# PCB_Schematic.net
KiCad netlist of a schematic drawn in Altium Designer
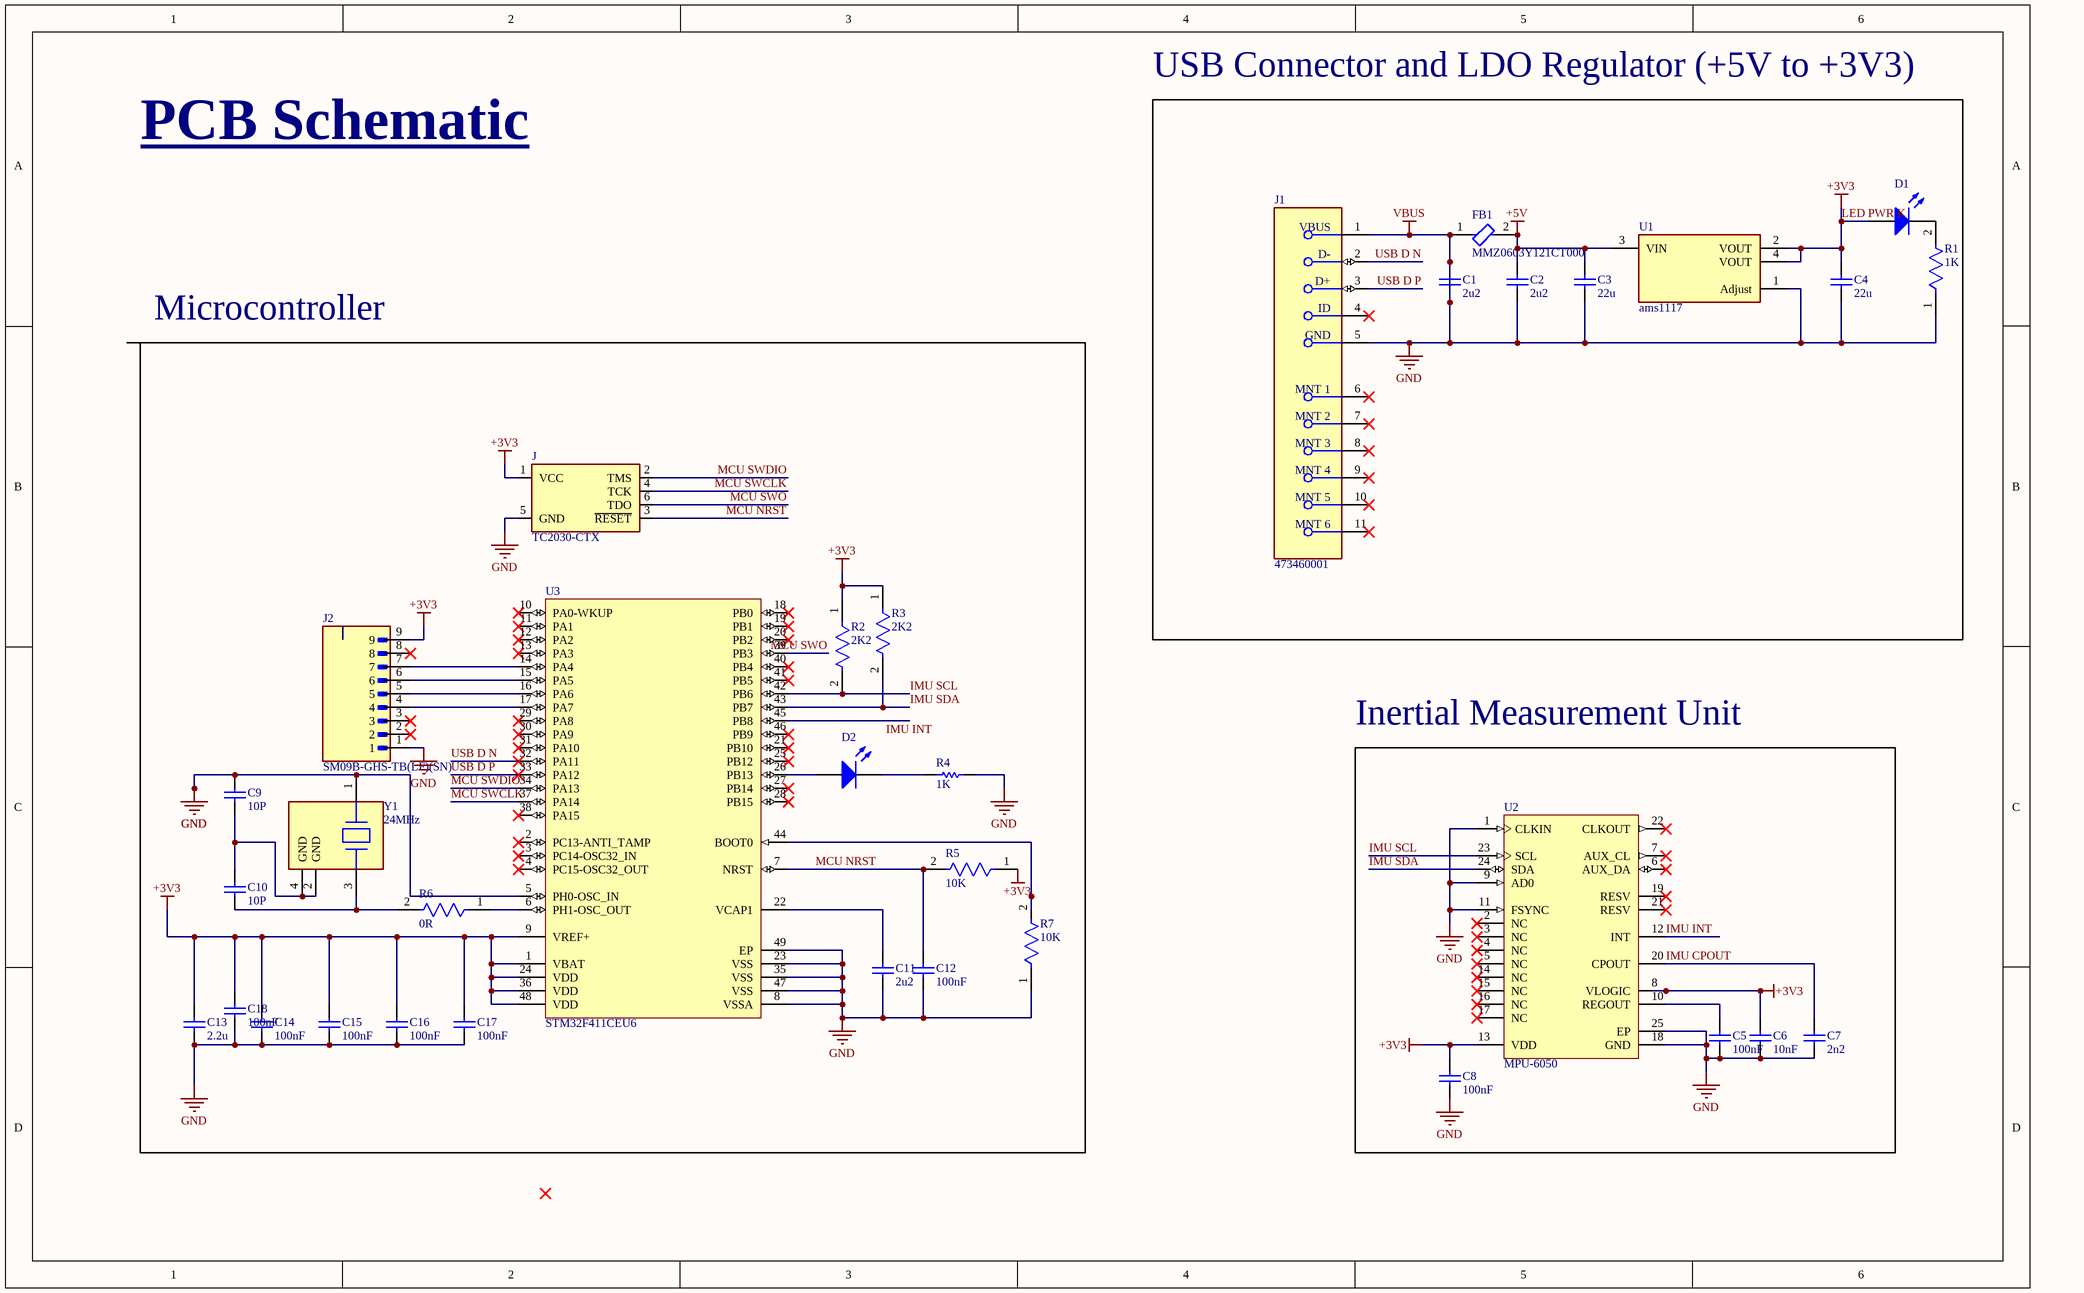
[diagram p0: PCB Schematic.SchDoc]

(export (version "E")
  (design (tool "Eeschema 10.0.6"))
  (components
    (comp (ref "C1")
      (value "2u2")
      (footprint "CAPC1210(3225)100_L")
      (description "CAP 100nF 16V ±5% 1210 (3225 Metric) Thickness 1mm SMD")
      (fields (field (name "TOLERANCE") "Â±5%"))
      (libsource (lib "Altium Content Vault") (part "CAP"))
    )
    (comp (ref "C2")
      (value "2u2")
      (footprint "CAPC1210(3225)100_L")
      (description "CAP 100nF 16V ±5% 1210 (3225 Metric) Thickness 1mm SMD")
      (fields (field (name "TOLERANCE") "Â±5%"))
      (libsource (lib "Altium Content Vault") (part "CAP"))
    )
    (comp (ref "C3")
      (value "22u")
      (footprint "CAPC1210(3225)100_L")
      (description "CAP 100nF 16V ±5% 1210 (3225 Metric) Thickness 1mm SMD")
      (fields (field (name "TOLERANCE") "Â±5%"))
      (libsource (lib "Altium Content Vault") (part "CAP"))
    )
    (comp (ref "C4")
      (value "22u")
      (footprint "CAPC1210(3225)100_L")
      (description "CAP 100nF 16V ±5% 1210 (3225 Metric) Thickness 1mm SMD")
      (fields (field (name "TOLERANCE") "Â±5%"))
      (libsource (lib "Altium Content Vault") (part "CAP"))
    )
    (comp (ref "C5")
      (value "100nF")
      (footprint "CAPC1210(3225)100_L")
      (description "CAP 100nF 16V ±5% 1210 (3225 Metric) Thickness 1mm SMD")
      (fields (field (name "TOLERANCE") "Â±5%"))
      (libsource (lib "Altium Content Vault") (part "CAP"))
    )
    (comp (ref "C6")
      (value "10nF")
      (footprint "CAPC1210(3225)100_L")
      (description "CAP 100nF 16V ±5% 1210 (3225 Metric) Thickness 1mm SMD")
      (fields (field (name "TOLERANCE") "Â±5%"))
      (libsource (lib "Altium Content Vault") (part "CAP"))
    )
    (comp (ref "C7")
      (value "2n2")
      (footprint "CAPC1210(3225)100_L")
      (description "CAP 100nF 16V ±5% 1210 (3225 Metric) Thickness 1mm SMD")
      (fields (field (name "TOLERANCE") "Â±5%"))
      (libsource (lib "Altium Content Vault") (part "CAP"))
    )
    (comp (ref "C8")
      (value "100nF")
      (footprint "CAPC1210(3225)100_L")
      (description "CAP 100nF 16V ±5% 1210 (3225 Metric) Thickness 1mm SMD")
      (fields (field (name "TOLERANCE") "Â±5%"))
      (libsource (lib "Altium Content Vault") (part "CAP"))
    )
    (comp (ref "C9")
      (value "10P")
      (footprint "CAPC1210(3225)100_L")
      (description "2.2u")
      (fields (field (name "TOLERANCE") "Â±5%"))
      (libsource (lib "Altium Content Vault") (part "CAP"))
    )
    (comp (ref "C10")
      (value "10P")
      (footprint "CAPC1210(3225)100_L")
      (description "2.2u")
      (fields (field (name "TOLERANCE") "Â±5%"))
      (libsource (lib "Altium Content Vault") (part "CAP"))
    )
    (comp (ref "C11")
      (value "2u2")
      (footprint "CAPC1210(3225)100_L")
      (description "CAP 100nF 16V ±5% 1210 (3225 Metric) Thickness 1mm SMD")
      (fields (field (name "TOLERANCE") "Â±5%"))
      (libsource (lib "Altium Content Vault") (part "CAP"))
    )
    (comp (ref "C12")
      (value "100nF")
      (footprint "CAPC1210(3225)100_L")
      (description "CAP 100nF 16V ±5% 1210 (3225 Metric) Thickness 1mm SMD")
      (fields (field (name "TOLERANCE") "Â±5%"))
      (libsource (lib "Altium Content Vault") (part "CAP"))
    )
    (comp (ref "C13")
      (value "2.2u")
      (footprint "CAPC1210(3225)100_L")
      (fields (field (name "TOLERANCE") "Â±5%"))
      (libsource (lib "Altium Content Vault") (part "CAP"))
    )
    (comp (ref "C14")
      (value "100nF")
      (footprint "CAPC1210(3225)100_L")
      (fields (field (name "TOLERANCE") "Â±5%"))
      (libsource (lib "Altium Content Vault") (part "CAP"))
    )
    (comp (ref "C15")
      (value "100nF")
      (footprint "CAPC1210(3225)100_L")
      (fields (field (name "TOLERANCE") "Â±5%"))
      (libsource (lib "Altium Content Vault") (part "CAP"))
    )
    (comp (ref "C16")
      (value "100nF")
      (footprint "CAPC1210(3225)100_L")
      (fields (field (name "TOLERANCE") "Â±5%"))
      (libsource (lib "Altium Content Vault") (part "CAP"))
    )
    (comp (ref "C17")
      (value "100nF")
      (footprint "CAPC1210(3225)100_L")
      (description "CAP 100nF 16V ±5% 1210 (3225 Metric) Thickness 1mm SMD")
      (fields (field (name "TOLERANCE") "Â±5%"))
      (libsource (lib "Altium Content Vault") (part "CAP"))
    )
    (comp (ref "C18")
      (value "100nF")
      (footprint "CAPC1210(3225)100_L")
      (fields (field (name "TOLERANCE") "Â±5%"))
      (libsource (lib "Altium Content Vault") (part "CAP"))
    )
    (comp (ref "D1")
      (value "Light-Emitting Diode")
      (libsource (lib "Simulation Generic Components") (part "LED"))
    )
    (comp (ref "D2")
      (value "Light-Emitting Diode")
      (libsource (lib "Simulation Generic Components") (part "LED"))
    )
    (comp (ref "FB1")
      (value "MMZ0603Y121CT000")
      (footprint "FP-MMZ0603-IPC_C")
      (description "Signal Line Ferrite Bead 120Ω @ 100MHz 200mA DCR 390mΩ SMD 0201")
      (fields (field (name "TOLERANCE") "25%"))
      (libsource (lib "Altium Content Vault") (part "5f30dd21d616792df468990f7003faa"))
    )
    (comp (ref "J")
      (value "TC2030-CTX")
      (footprint "TC2030-IDC-NL")
      (description "CortexÂ® Plug-Of-Nailsâ„¢ Adapter Cable")
      (fields (field (name "MF") "Tag-Connect LLC"))
      (libsource (lib "TC2030-CTX") (part "TC2030-CTX"))
    )
    (comp (ref "J1")
      (value "473460001")
      (footprint "FP-473460001-MFG")
      (description "USB - micro B USB 2.0 Receptacle Connector 5 Position Surface Mount, Right Angle")
      (fields (field (name "OCTOPART") "https://octopart.com/47346-0001-molex-7164928"))
      (libsource (lib "Altium Content Vault") (part "53ae1f1d9b557310b43ca686e5bb76a"))
    )
    (comp (ref "J2")
      (value "SM09B-GHS-TB(LF)(SN)")
      (footprint "JST_SM09B-GHS-TB(LF)(SN)")
      (fields (field (name "MF") "JST") (field (name "MP") "SM09B-GHS-TB (LF)(SN)"))
      (libsource (lib "SM09B-GHS-TB_LF__SN_") (part "SM09B-GHS-TB(LF)(SN)"))
    )
    (comp (ref "R1")
      (value "1K")
      (footprint "FP-AC0603-IPC_A")
      (description "RES 10kΩ 5.00% 0.2W 0603")
      (libsource (lib "Altium Content Vault") (part "1029c3af85768c4190bb7ad29bc67b5"))
    )
    (comp (ref "R2")
      (value "2K2")
      (footprint "FP-AC0603-IPC_A")
      (description "RES 10kΩ 5.00% 0.2W 0603")
      (libsource (lib "Altium Content Vault") (part "1029c3af85768c4190bb7ad29bc67b5"))
    )
    (comp (ref "R3")
      (value "2K2")
      (footprint "FP-AC0603-IPC_A")
      (description "RES 10kΩ 5.00% 0.2W 0603")
      (libsource (lib "Altium Content Vault") (part "1029c3af85768c4190bb7ad29bc67b5"))
    )
    (comp (ref "R4")
      (value "1K")
      (description "Resistor")
      (libsource (lib "Simulation Generic Components") (part "Resistor"))
    )
    (comp (ref "R5")
      (value "10K")
      (footprint "FP-AC0603-IPC_A")
      (description "RES 10kΩ 5.00% 0.2W 0603")
      (libsource (lib "Altium Content Vault") (part "1029c3af85768c4190bb7ad29bc67b5"))
    )
    (comp (ref "R6")
      (value "0R")
      (footprint "FP-AC0603-IPC_A")
      (description "RES 10kΩ 5.00% 0.2W 0603")
      (libsource (lib "Altium Content Vault") (part "1029c3af85768c4190bb7ad29bc67b5"))
    )
    (comp (ref "R7")
      (value "10K")
      (footprint "FP-AC0603-IPC_A")
      (description "RES 10kΩ 5.00% 0.2W 0603")
      (libsource (lib "Altium Content Vault") (part "1029c3af85768c4190bb7ad29bc67b5"))
    )
    (comp (ref "U1")
      (value "ams1117")
      (footprint "FP-ams1117-IPC_C")
      (description "1A LOW DROPOUT VOLTAGE REGULATOR")
      (libsource (lib "Altium Content Vault") (part "59ad430b93a2c51b3e6ee7c3b069677"))
    )
    (comp (ref "U2")
      (value "MPU-6050")
      (footprint "IS-QFN-24_V")
      (fields (field (name "MANUFACTURER") "InvenSense"))
      (libsource (lib "Altium Content Vault") (part "IS-MPU-6050-QFN-24"))
    )
    (comp (ref "U3")
      (value "STM32F411CEU6")
      (footprint "STM-UFQFPN48_L")
      (libsource (lib "Altium Content Vault") (part "MC-ARM-STM32F411-UFQFPN48"))
    )
    (comp (ref "Y1")
      (value "24MHz")
      (footprint "FP-ABM10AIG-MFG")
      (description "Crystal 24MHz ±30ppm 10pF SMD-4 2.5mm x 2mm Automotive")
      (libsource (lib "Altium Content Vault") (part "40c3c19da1ce8e2d75e34138d1085e7"))
    )
  )
  (nets
    (net (code "1") (name "+3V3") (class "Default")
      (node (ref "C13") (pin "2") (pinfunction "2_2") (pintype "passive"))
      (node (ref "C14") (pin "2") (pinfunction "2_2") (pintype "passive"))
      (node (ref "C15") (pin "2") (pinfunction "2_2") (pintype "passive"))
      (node (ref "C16") (pin "2") (pinfunction "2_2") (pintype "passive"))
      (node (ref "C17") (pin "2") (pinfunction "2_2") (pintype "passive"))
      (node (ref "C18") (pin "2") (pinfunction "2_2") (pintype "passive"))
      (node (ref "C4") (pin "2") (pinfunction "2_2") (pintype "passive"))
      (node (ref "C6") (pin "2") (pinfunction "2_2") (pintype "passive"))
      (node (ref "C8") (pin "2") (pinfunction "2_2") (pintype "passive"))
      (node (ref "D1") (pin "1") (pinfunction "A_1") (pintype "passive"))
      (node (ref "J") (pin "1") (pinfunction "VCC_1") (pintype "bidirectional"))
      (node (ref "J2") (pin "9") (pinfunction "9_9") (pintype "passive"))
      (node (ref "R2") (pin "1") (pinfunction "1_1") (pintype "passive"))
      (node (ref "R3") (pin "1") (pinfunction "1_1") (pintype "passive"))
      (node (ref "R5") (pin "1") (pinfunction "1_1") (pintype "passive"))
      (node (ref "U1") (pin "2") (pinfunction "VOUT_2") (pintype "passive"))
      (node (ref "U1") (pin "4") (pinfunction "VOUT_4") (pintype "passive"))
      (node (ref "U2") (pin "13") (pinfunction "VDD_13") (pintype "power_in"))
      (node (ref "U2") (pin "8") (pinfunction "VLOGIC_8") (pintype "power_in"))
      (node (ref "U3") (pin "1") (pinfunction "VBAT_1") (pintype "power_in"))
      (node (ref "U3") (pin "24") (pinfunction "VDD_24") (pintype "power_in"))
      (node (ref "U3") (pin "36") (pinfunction "VDD_36") (pintype "power_in"))
      (node (ref "U3") (pin "48") (pinfunction "VDD_48") (pintype "power_in"))
      (node (ref "U3") (pin "9") (pinfunction "VREF+_9") (pintype "power_in"))
    )
    (net (code "2") (name "+5V") (class "Default")
      (node (ref "C2") (pin "2") (pinfunction "2_2") (pintype "passive"))
      (node (ref "C3") (pin "2") (pinfunction "2_2") (pintype "passive"))
      (node (ref "FB1") (pin "2") (pinfunction "2_2") (pintype "passive"))
      (node (ref "U1") (pin "3") (pinfunction "VIN_3") (pintype "power_in"))
    )
    (net (code "3") (name "/IMU CPOUT") (class "Default")
      (node (ref "C7") (pin "2") (pinfunction "2_2") (pintype "passive"))
      (node (ref "U2") (pin "20") (pinfunction "CPOUT_20") (pintype "passive"))
    )
    (net (code "4") (name "/IMU INT") (class "Default")
      (node (ref "U2") (pin "12") (pinfunction "INT_12") (pintype "open_collector"))
      (node (ref "U3") (pin "45") (pinfunction "PB8_45") (pintype "bidirectional"))
    )
    (net (code "5") (name "/IMU SCL") (class "Default")
      (node (ref "R2") (pin "2") (pinfunction "2_2") (pintype "passive"))
      (node (ref "U2") (pin "23") (pinfunction "SCL_23") (pintype "input"))
      (node (ref "U3") (pin "42") (pinfunction "PB6_42") (pintype "bidirectional"))
    )
    (net (code "6") (name "/IMU SDA") (class "Default")
      (node (ref "R3") (pin "2") (pinfunction "2_2") (pintype "passive"))
      (node (ref "U2") (pin "24") (pinfunction "SDA_24") (pintype "bidirectional"))
      (node (ref "U3") (pin "43") (pinfunction "PB7_43") (pintype "bidirectional"))
    )
    (net (code "7") (name "/MCU NRST") (class "Default")
      (node (ref "C12") (pin "2") (pinfunction "2_2") (pintype "passive"))
      (node (ref "J") (pin "3") (pinfunction "~{RESET}_3") (pintype "bidirectional"))
      (node (ref "R5") (pin "2") (pinfunction "2_2") (pintype "passive"))
      (node (ref "U3") (pin "7") (pinfunction "NRST_7") (pintype "bidirectional"))
    )
    (net (code "8") (name "/MCU SWCLK") (class "Default")
      (node (ref "J") (pin "4") (pinfunction "TCK_4") (pintype "bidirectional"))
      (node (ref "U3") (pin "37") (pinfunction "PA14_37") (pintype "bidirectional"))
    )
    (net (code "9") (name "/MCU SWDIO") (class "Default")
      (node (ref "J") (pin "2") (pinfunction "TMS_2") (pintype "bidirectional"))
      (node (ref "U3") (pin "34") (pinfunction "PA13_34") (pintype "bidirectional"))
    )
    (net (code "10") (name "/MCU SWO") (class "Default")
      (node (ref "J") (pin "6") (pinfunction "TDO_6") (pintype "bidirectional"))
      (node (ref "U3") (pin "39") (pinfunction "PB3_39") (pintype "bidirectional"))
    )
    (net (code "11") (name "/USB D N") (class "Default")
      (node (ref "J1") (pin "2") (pinfunction "D-_2") (pintype "bidirectional"))
      (node (ref "U3") (pin "32") (pinfunction "PA11_32") (pintype "bidirectional"))
    )
    (net (code "12") (name "/USB D P") (class "Default")
      (node (ref "J1") (pin "3") (pinfunction "D+_3") (pintype "bidirectional"))
      (node (ref "U3") (pin "33") (pinfunction "PA12_33") (pintype "bidirectional"))
    )
    (net (code "13") (name "GND") (class "Default")
      (node (ref "C1") (pin "1") (pinfunction "1_1") (pintype "passive"))
      (node (ref "C1") (pin "2") (pinfunction "2_2") (pintype "passive"))
      (node (ref "C11") (pin "1") (pinfunction "1_1") (pintype "passive"))
      (node (ref "C12") (pin "1") (pinfunction "1_1") (pintype "passive"))
      (node (ref "C13") (pin "1") (pinfunction "1_1") (pintype "passive"))
      (node (ref "C14") (pin "1") (pinfunction "1_1") (pintype "passive"))
      (node (ref "C15") (pin "1") (pinfunction "1_1") (pintype "passive"))
      (node (ref "C16") (pin "1") (pinfunction "1_1") (pintype "passive"))
      (node (ref "C17") (pin "1") (pinfunction "1_1") (pintype "passive"))
      (node (ref "C18") (pin "1") (pinfunction "1_1") (pintype "passive"))
      (node (ref "C2") (pin "1") (pinfunction "1_1") (pintype "passive"))
      (node (ref "C3") (pin "1") (pinfunction "1_1") (pintype "passive"))
      (node (ref "C4") (pin "1") (pinfunction "1_1") (pintype "passive"))
      (node (ref "C5") (pin "1") (pinfunction "1_1") (pintype "passive"))
      (node (ref "C6") (pin "1") (pinfunction "1_1") (pintype "passive"))
      (node (ref "C7") (pin "1") (pinfunction "1_1") (pintype "passive"))
      (node (ref "C8") (pin "1") (pinfunction "1_1") (pintype "passive"))
      (node (ref "C9") (pin "1") (pinfunction "1_1") (pintype "passive"))
      (node (ref "FB1") (pin "1") (pinfunction "1_1") (pintype "passive"))
      (node (ref "J") (pin "5") (pinfunction "GND_5") (pintype "bidirectional"))
      (node (ref "J1") (pin "1") (pinfunction "VBUS_1") (pintype "power_in"))
      (node (ref "J1") (pin "5") (pinfunction "GND_5") (pintype "power_in"))
      (node (ref "J2") (pin "1") (pinfunction "1_1") (pintype "passive"))
      (node (ref "R1") (pin "1") (pinfunction "1_1") (pintype "passive"))
      (node (ref "R4") (pin "1") (pinfunction "1_1") (pintype "passive"))
      (node (ref "R7") (pin "1") (pinfunction "1_1") (pintype "passive"))
      (node (ref "U1") (pin "1") (pinfunction "Adjust_1") (pintype "passive"))
      (node (ref "U2") (pin "1") (pinfunction "CLKIN_1") (pintype "input"))
      (node (ref "U2") (pin "11") (pinfunction "FSYNC_11") (pintype "input"))
      (node (ref "U2") (pin "18") (pinfunction "GND_18") (pintype "power_in"))
      (node (ref "U2") (pin "25") (pinfunction "EP_25") (pintype "power_in"))
      (node (ref "U2") (pin "9") (pinfunction "AD0_9") (pintype "input"))
      (node (ref "U3") (pin "23") (pinfunction "VSS_23") (pintype "power_in"))
      (node (ref "U3") (pin "35") (pinfunction "VSS_35") (pintype "power_in"))
      (node (ref "U3") (pin "47") (pinfunction "VSS_47") (pintype "power_in"))
      (node (ref "U3") (pin "49") (pinfunction "EP_49") (pintype "power_in"))
      (node (ref "U3") (pin "5") (pinfunction "PH0-OSC_IN_5") (pintype "bidirectional"))
      (node (ref "U3") (pin "8") (pinfunction "VSSA_8") (pintype "power_in"))
      (node (ref "Y1") (pin "1") (pinfunction "1_Crystal_1") (pintype "passive"))
    )
    (net (code "14") (name "Net-(C10-Pad1)") (class "Default")
      (node (ref "C10") (pin "1") (pinfunction "1_1") (pintype "passive"))
      (node (ref "C9") (pin "2") (pinfunction "2_2") (pintype "passive"))
      (node (ref "Y1") (pin "2") (pinfunction "GND_2") (pintype "power_in"))
      (node (ref "Y1") (pin "4") (pinfunction "GND_4") (pintype "power_in"))
    )
    (net (code "15") (name "Net-(D1-K)") (class "Default")
      (node (ref "D1") (pin "2") (pinfunction "K_2") (pintype "passive"))
      (node (ref "R1") (pin "2") (pinfunction "2_2") (pintype "passive"))
    )
    (net (code "16") (name "Net-(D2-A)") (class "Default")
      (node (ref "D2") (pin "1") (pinfunction "A_1") (pintype "passive"))
      (node (ref "U3") (pin "26") (pinfunction "PB13_26") (pintype "bidirectional"))
    )
    (net (code "17") (name "Net-(D2-K)") (class "Default")
      (node (ref "D2") (pin "2") (pinfunction "K_2") (pintype "passive"))
      (node (ref "R4") (pin "2") (pinfunction "2_2") (pintype "passive"))
    )
    (net (code "18") (name "Net-(U2-REGOUT)") (class "Default")
      (node (ref "C5") (pin "2") (pinfunction "2_2") (pintype "passive"))
      (node (ref "U2") (pin "10") (pinfunction "REGOUT_10") (pintype "passive"))
    )
    (net (code "19") (name "Net-(U3-BOOT0)") (class "Default")
      (node (ref "R7") (pin "2") (pinfunction "2_2") (pintype "passive"))
      (node (ref "U3") (pin "44") (pinfunction "BOOT0_44") (pintype "input"))
    )
    (net (code "20") (name "Net-(U3-PA4)") (class "Default")
      (node (ref "J2") (pin "7") (pinfunction "7_7") (pintype "passive"))
      (node (ref "U3") (pin "14") (pinfunction "PA4_14") (pintype "bidirectional"))
    )
    (net (code "21") (name "Net-(U3-PA5)") (class "Default")
      (node (ref "J2") (pin "6") (pinfunction "6_6") (pintype "passive"))
      (node (ref "U3") (pin "15") (pinfunction "PA5_15") (pintype "bidirectional"))
    )
    (net (code "22") (name "Net-(U3-PA6)") (class "Default")
      (node (ref "J2") (pin "5") (pinfunction "5_5") (pintype "passive"))
      (node (ref "U3") (pin "16") (pinfunction "PA6_16") (pintype "bidirectional"))
    )
    (net (code "23") (name "Net-(U3-PA7)") (class "Default")
      (node (ref "J2") (pin "4") (pinfunction "4_4") (pintype "passive"))
      (node (ref "U3") (pin "17") (pinfunction "PA7_17") (pintype "bidirectional"))
    )
    (net (code "24") (name "Net-(U3-PH1-OSC_OUT)") (class "Default")
      (node (ref "R6") (pin "1") (pinfunction "1_1") (pintype "passive"))
      (node (ref "U3") (pin "6") (pinfunction "PH1-OSC_OUT_6") (pintype "bidirectional"))
    )
    (net (code "25") (name "Net-(U3-VCAP1)") (class "Default")
      (node (ref "C11") (pin "2") (pinfunction "2_2") (pintype "passive"))
      (node (ref "U3") (pin "22") (pinfunction "VCAP1_22") (pintype "passive"))
    )
    (net (code "26") (name "Net-(Y1-2_Crystal)") (class "Default")
      (node (ref "C10") (pin "2") (pinfunction "2_2") (pintype "passive"))
      (node (ref "R6") (pin "2") (pinfunction "2_2") (pintype "passive"))
      (node (ref "Y1") (pin "3") (pinfunction "2_Crystal_3") (pintype "passive"))
    )
    (net (code "27") (name "unconnected-(J1-ID-Pad4)") (class "Default")
      (node (ref "J1") (pin "4") (pinfunction "ID_4") (pintype "passive+no_connect"))
    )
    (net (code "28") (name "unconnected-(J1-MNT_1-Pad6)") (class "Default")
      (node (ref "J1") (pin "6") (pinfunction "MNT_1_6") (pintype "passive+no_connect"))
    )
    (net (code "29") (name "unconnected-(J1-MNT_2-Pad7)") (class "Default")
      (node (ref "J1") (pin "7") (pinfunction "MNT_2_7") (pintype "passive+no_connect"))
    )
    (net (code "30") (name "unconnected-(J1-MNT_3-Pad8)") (class "Default")
      (node (ref "J1") (pin "8") (pinfunction "MNT_3_8") (pintype "passive+no_connect"))
    )
    (net (code "31") (name "unconnected-(J1-MNT_4-Pad9)") (class "Default")
      (node (ref "J1") (pin "9") (pinfunction "MNT_4_9") (pintype "passive+no_connect"))
    )
    (net (code "32") (name "unconnected-(J1-MNT_5-Pad10)") (class "Default")
      (node (ref "J1") (pin "10") (pinfunction "MNT_5_10") (pintype "passive+no_connect"))
    )
    (net (code "33") (name "unconnected-(J1-MNT_6-Pad11)") (class "Default")
      (node (ref "J1") (pin "11") (pinfunction "MNT_6_11") (pintype "passive+no_connect"))
    )
    (net (code "34") (name "unconnected-(J2-Pad2)") (class "Default")
      (node (ref "J2") (pin "2") (pinfunction "2_2") (pintype "passive+no_connect"))
    )
    (net (code "35") (name "unconnected-(J2-Pad3)") (class "Default")
      (node (ref "J2") (pin "3") (pinfunction "3_3") (pintype "passive+no_connect"))
    )
    (net (code "36") (name "unconnected-(J2-Pad8)") (class "Default")
      (node (ref "J2") (pin "8") (pinfunction "8_8") (pintype "passive+no_connect"))
    )
    (net (code "37") (name "unconnected-(U2-AUX_CL-Pad7)") (class "Default")
      (node (ref "U2") (pin "7") (pinfunction "AUX_CL_7") (pintype "output+no_connect"))
    )
    (net (code "38") (name "unconnected-(U2-AUX_DA-Pad6)") (class "Default")
      (node (ref "U2") (pin "6") (pinfunction "AUX_DA_6") (pintype "bidirectional+no_connect"))
    )
    (net (code "39") (name "unconnected-(U2-CLKOUT-Pad22)") (class "Default")
      (node (ref "U2") (pin "22") (pinfunction "CLKOUT_22") (pintype "output+no_connect"))
    )
    (net (code "40") (name "unconnected-(U2-NC-Pad2)") (class "Default")
      (node (ref "U2") (pin "2") (pinfunction "NC_2") (pintype "passive+no_connect"))
    )
    (net (code "41") (name "unconnected-(U2-NC-Pad3)") (class "Default")
      (node (ref "U2") (pin "3") (pinfunction "NC_3") (pintype "passive+no_connect"))
    )
    (net (code "42") (name "unconnected-(U2-NC-Pad4)") (class "Default")
      (node (ref "U2") (pin "4") (pinfunction "NC_4") (pintype "passive+no_connect"))
    )
    (net (code "43") (name "unconnected-(U2-NC-Pad5)") (class "Default")
      (node (ref "U2") (pin "5") (pinfunction "NC_5") (pintype "passive+no_connect"))
    )
    (net (code "44") (name "unconnected-(U2-NC-Pad14)") (class "Default")
      (node (ref "U2") (pin "14") (pinfunction "NC_14") (pintype "passive+no_connect"))
    )
    (net (code "45") (name "unconnected-(U2-NC-Pad15)") (class "Default")
      (node (ref "U2") (pin "15") (pinfunction "NC_15") (pintype "passive+no_connect"))
    )
    (net (code "46") (name "unconnected-(U2-NC-Pad16)") (class "Default")
      (node (ref "U2") (pin "16") (pinfunction "NC_16") (pintype "passive+no_connect"))
    )
    (net (code "47") (name "unconnected-(U2-NC-Pad17)") (class "Default")
      (node (ref "U2") (pin "17") (pinfunction "NC_17") (pintype "passive+no_connect"))
    )
    (net (code "48") (name "unconnected-(U2-RESV-Pad19)") (class "Default")
      (node (ref "U2") (pin "19") (pinfunction "RESV_19") (pintype "passive+no_connect"))
    )
    (net (code "49") (name "unconnected-(U2-RESV-Pad21)") (class "Default")
      (node (ref "U2") (pin "21") (pinfunction "RESV_21") (pintype "passive+no_connect"))
    )
    (net (code "50") (name "unconnected-(U3-PA0-WKUP-Pad10)") (class "Default")
      (node (ref "U3") (pin "10") (pinfunction "PA0-WKUP_10") (pintype "bidirectional+no_connect"))
    )
    (net (code "51") (name "unconnected-(U3-PA1-Pad11)") (class "Default")
      (node (ref "U3") (pin "11") (pinfunction "PA1_11") (pintype "bidirectional+no_connect"))
    )
    (net (code "52") (name "unconnected-(U3-PA2-Pad12)") (class "Default")
      (node (ref "U3") (pin "12") (pinfunction "PA2_12") (pintype "bidirectional+no_connect"))
    )
    (net (code "53") (name "unconnected-(U3-PA3-Pad13)") (class "Default")
      (node (ref "U3") (pin "13") (pinfunction "PA3_13") (pintype "bidirectional+no_connect"))
    )
    (net (code "54") (name "unconnected-(U3-PA8-Pad29)") (class "Default")
      (node (ref "U3") (pin "29") (pinfunction "PA8_29") (pintype "bidirectional+no_connect"))
    )
    (net (code "55") (name "unconnected-(U3-PA9-Pad30)") (class "Default")
      (node (ref "U3") (pin "30") (pinfunction "PA9_30") (pintype "bidirectional+no_connect"))
    )
    (net (code "56") (name "unconnected-(U3-PA10-Pad31)") (class "Default")
      (node (ref "U3") (pin "31") (pinfunction "PA10_31") (pintype "bidirectional+no_connect"))
    )
    (net (code "57") (name "unconnected-(U3-PA15-Pad38)") (class "Default")
      (node (ref "U3") (pin "38") (pinfunction "PA15_38") (pintype "bidirectional+no_connect"))
    )
    (net (code "58") (name "unconnected-(U3-PB0-Pad18)") (class "Default")
      (node (ref "U3") (pin "18") (pinfunction "PB0_18") (pintype "bidirectional+no_connect"))
    )
    (net (code "59") (name "unconnected-(U3-PB1-Pad19)") (class "Default")
      (node (ref "U3") (pin "19") (pinfunction "PB1_19") (pintype "bidirectional+no_connect"))
    )
    (net (code "60") (name "unconnected-(U3-PB2-Pad20)") (class "Default")
      (node (ref "U3") (pin "20") (pinfunction "PB2_20") (pintype "bidirectional+no_connect"))
    )
    (net (code "61") (name "unconnected-(U3-PB4-Pad40)") (class "Default")
      (node (ref "U3") (pin "40") (pinfunction "PB4_40") (pintype "bidirectional+no_connect"))
    )
    (net (code "62") (name "unconnected-(U3-PB5-Pad41)") (class "Default")
      (node (ref "U3") (pin "41") (pinfunction "PB5_41") (pintype "bidirectional+no_connect"))
    )
    (net (code "63") (name "unconnected-(U3-PB9-Pad46)") (class "Default")
      (node (ref "U3") (pin "46") (pinfunction "PB9_46") (pintype "bidirectional+no_connect"))
    )
    (net (code "64") (name "unconnected-(U3-PB10-Pad21)") (class "Default")
      (node (ref "U3") (pin "21") (pinfunction "PB10_21") (pintype "bidirectional+no_connect"))
    )
    (net (code "65") (name "unconnected-(U3-PB12-Pad25)") (class "Default")
      (node (ref "U3") (pin "25") (pinfunction "PB12_25") (pintype "bidirectional+no_connect"))
    )
    (net (code "66") (name "unconnected-(U3-PB14-Pad27)") (class "Default")
      (node (ref "U3") (pin "27") (pinfunction "PB14_27") (pintype "bidirectional+no_connect"))
    )
    (net (code "67") (name "unconnected-(U3-PB15-Pad28)") (class "Default")
      (node (ref "U3") (pin "28") (pinfunction "PB15_28") (pintype "bidirectional+no_connect"))
    )
    (net (code "68") (name "unconnected-(U3-PC13-ANTI_TAMP-Pad2)") (class "Default")
      (node (ref "U3") (pin "2") (pinfunction "PC13-ANTI_TAMP_2") (pintype "bidirectional+no_connect"))
    )
    (net (code "69") (name "unconnected-(U3-PC14-OSC32_IN-Pad3)") (class "Default")
      (node (ref "U3") (pin "3") (pinfunction "PC14-OSC32_IN_3") (pintype "bidirectional+no_connect"))
    )
    (net (code "70") (name "unconnected-(U3-PC15-OSC32_OUT-Pad4)") (class "Default")
      (node (ref "U3") (pin "4") (pinfunction "PC15-OSC32_OUT_4") (pintype "bidirectional+no_connect"))
    )
  )
)
